# ProProject_FPC_HDC302x_LPS22_2024-05-12.net
KiCad netlist of a schematic drawn in EasyEDA Pro
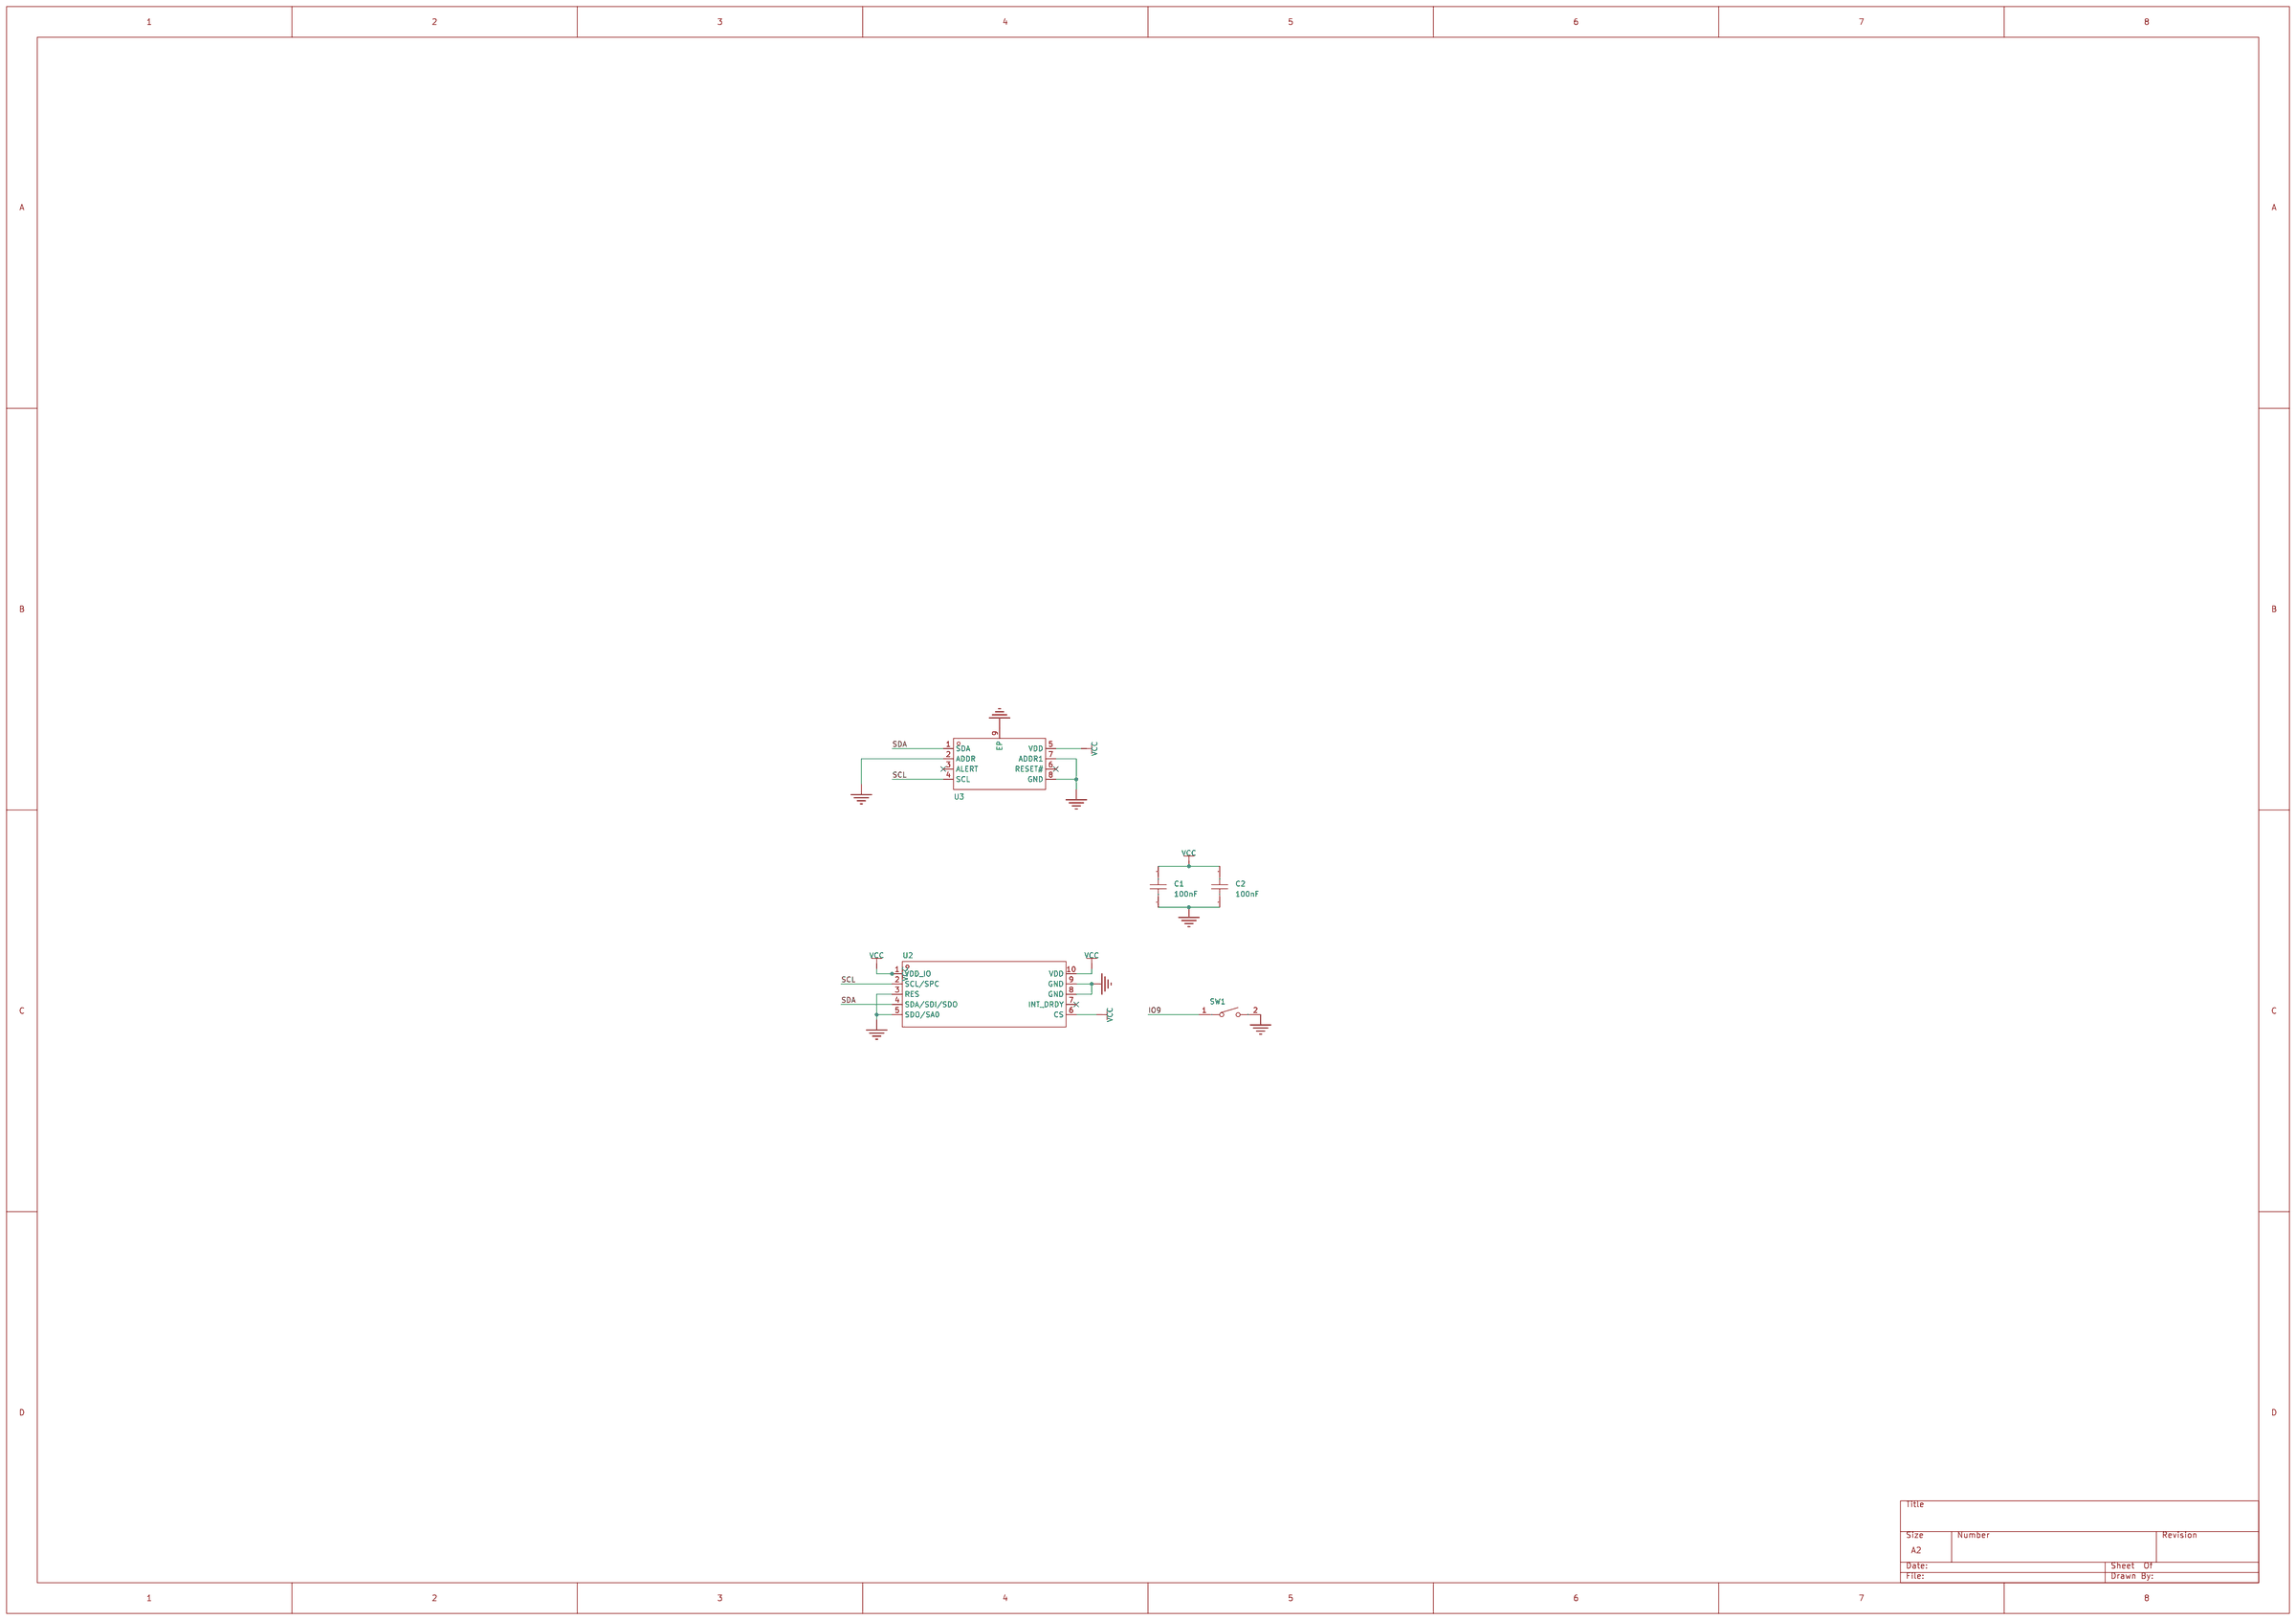
[diagram p0: schematic sheet]

(export (version "E")
  (design (tool "Eeschema 10.0.6"))
  (components
    (comp (ref "C1")
      (value "100nF")
      (footprint "easyedapro:C0402")
      (libsource (lib "easyedapro") (part "CapAcitance"))
    )
    (comp (ref "C2")
      (value "100nF")
      (footprint "easyedapro:C0402")
      (libsource (lib "easyedapro") (part "CapAcitance"))
    )
    (comp (ref "SW1")
      (value "TS-1088-AR02016")
      (footprint "easyedapro:SW-SMD_L3.9-W3.0-P4.45")
      (fields (field (name "Manufacturer") "XUNPU(讯普)"))
      (libsource (lib "easyedapro") (part "TS-1088-AR02016"))
    )
    (comp (ref "U2")
      (value "LPS22HBTR")
      (footprint "easyedapro:HLGA-10L_LPS22HBTR")
      (description "压力范围:26Kpa~126Kpa;")
      (fields (field (name "Manufacturer") "ST(意法半导体)"))
      (libsource (lib "easyedapro") (part "LPS22HBTR"))
    )
    (comp (ref "U3")
      (value "HDC3022DEJR")
      (footprint "easyedapro:TDFN-8_L2.5-W2.5-P0.50-BL-EP")
      (description "湿度：0%RH~100%RH")
      (fields (field (name "Manufacturer") "TI(德州仪器)"))
      (libsource (lib "easyedapro") (part "HDC3022DEJR"))
    )
  )
  (nets
    (net (code "1") (name "/IO9") (class "Default")
      (node (ref "SW1") (pin "1") (pinfunction "1_1") (pintype "unspecified"))
    )
    (net (code "2") (name "/SCL") (class "Default")
      (node (ref "U2") (pin "2") (pinfunction "SCL/SPC_2") (pintype "unspecified"))
      (node (ref "U3") (pin "4") (pinfunction "SCL_4") (pintype "unspecified"))
    )
    (net (code "3") (name "/SDA") (class "Default")
      (node (ref "U2") (pin "4") (pinfunction "SDA/SDI/SDO_4") (pintype "unspecified"))
      (node (ref "U3") (pin "1") (pinfunction "SDA_1") (pintype "unspecified"))
    )
    (net (code "4") (name "GND") (class "Default")
      (node (ref "C1") (pin "1") (pinfunction "1_1") (pintype "input"))
      (node (ref "C2") (pin "1") (pinfunction "1_1") (pintype "input"))
      (node (ref "SW1") (pin "2") (pinfunction "2_2") (pintype "unspecified"))
      (node (ref "U2") (pin "3") (pinfunction "RES_3") (pintype "unspecified"))
      (node (ref "U2") (pin "5") (pinfunction "SDO/SA0_5") (pintype "unspecified"))
      (node (ref "U2") (pin "8") (pinfunction "GND_8") (pintype "unspecified"))
      (node (ref "U2") (pin "9") (pinfunction "GND_9") (pintype "unspecified"))
      (node (ref "U3") (pin "2") (pinfunction "ADDR_2") (pintype "unspecified"))
      (node (ref "U3") (pin "7") (pinfunction "ADDR1_7") (pintype "unspecified"))
      (node (ref "U3") (pin "8") (pinfunction "GND_8") (pintype "unspecified"))
      (node (ref "U3") (pin "9") (pinfunction "EP_9") (pintype "unspecified"))
    )
    (net (code "5") (name "VCC") (class "Default")
      (node (ref "C1") (pin "2") (pinfunction "2_2") (pintype "input"))
      (node (ref "C2") (pin "2") (pinfunction "2_2") (pintype "input"))
      (node (ref "U2") (pin "1") (pinfunction "VDD_IO_1") (pintype "unspecified"))
      (node (ref "U2") (pin "10") (pinfunction "VDD_10") (pintype "unspecified"))
      (node (ref "U2") (pin "6") (pinfunction "CS_6") (pintype "unspecified"))
      (node (ref "U3") (pin "5") (pinfunction "VDD_5") (pintype "unspecified"))
    )
    (net (code "6") (name "unconnected-(U2-INT_DRDY-Pad7)") (class "Default")
      (node (ref "U2") (pin "7") (pinfunction "INT_DRDY_7") (pintype "unspecified+no_connect"))
    )
    (net (code "7") (name "unconnected-(U3-ALERT-Pad3)") (class "Default")
      (node (ref "U3") (pin "3") (pinfunction "ALERT_3") (pintype "unspecified+no_connect"))
    )
    (net (code "8") (name "unconnected-(U3-RESET#-Pad6)") (class "Default")
      (node (ref "U3") (pin "6") (pinfunction "RESET#_6") (pintype "unspecified+no_connect"))
    )
  )
)
